# HomeBoard.net
KiCad netlist of a schematic drawn in EAGLE
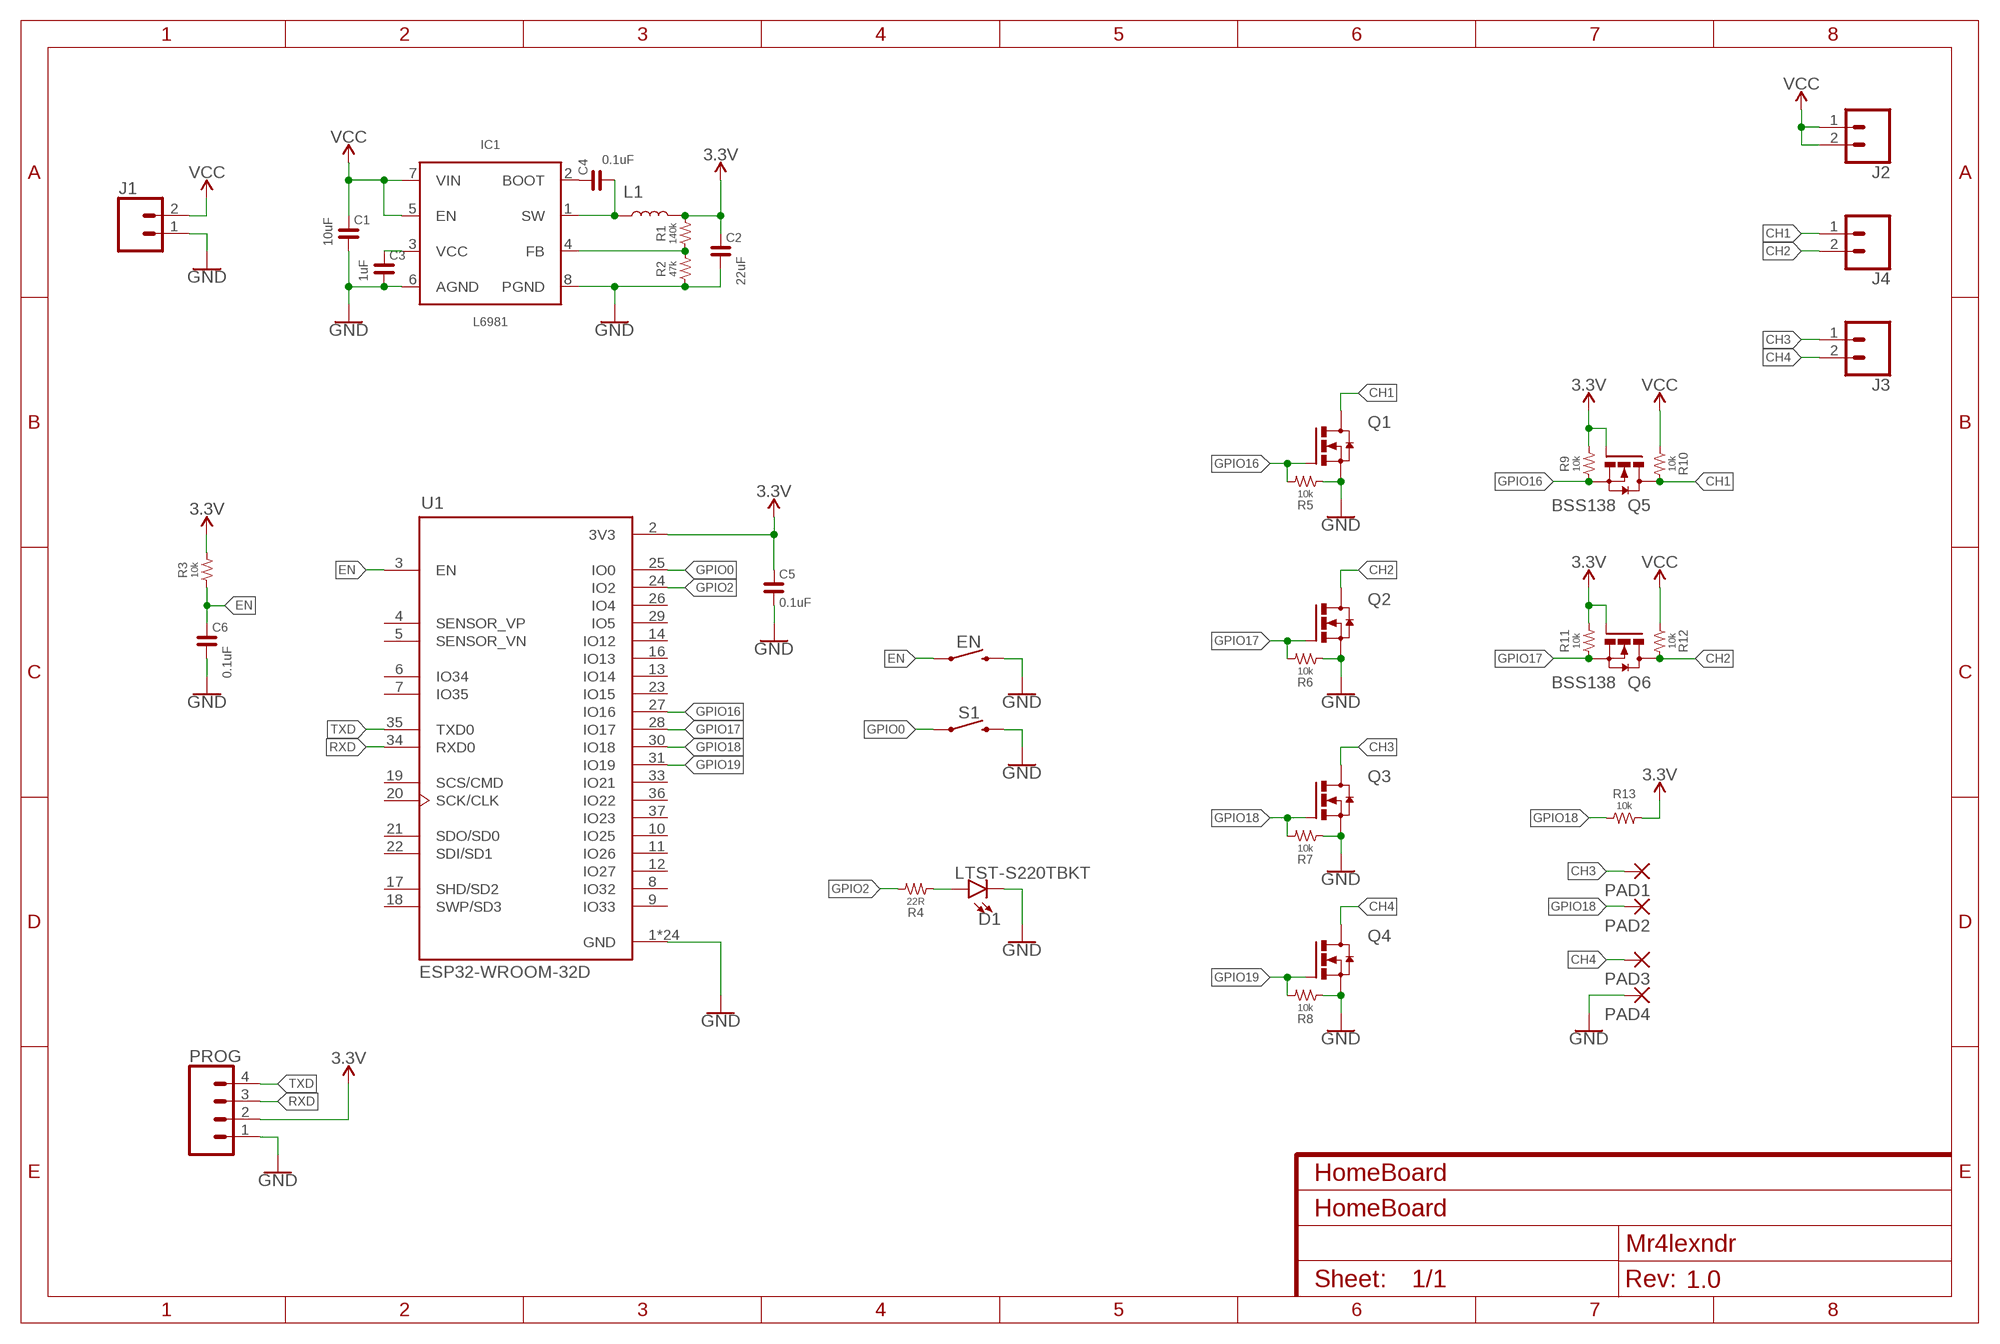
[diagram p0: schematic, sheet 1]

(export (version "E")
  (design (tool "Eeschema 10.0.6"))
  (components
    (comp (ref "C1")
      (value "10uF")
      (footprint "eagle-import:1206")
      (libsource (lib "eagle-import") (part "CAP-1206"))
    )
    (comp (ref "C2")
      (value "22uF")
      (footprint "eagle-import:1206")
      (libsource (lib "eagle-import") (part "CAP-1206"))
    )
    (comp (ref "C3")
      (value "1uF")
      (footprint "eagle-import:0603")
      (libsource (lib "eagle-import") (part "CAP-0603"))
    )
    (comp (ref "C4")
      (value "0.1uF")
      (footprint "eagle-import:0603")
      (libsource (lib "eagle-import") (part "CAP-0603"))
    )
    (comp (ref "C5")
      (value "0.1uF")
      (footprint "eagle-import:0603")
      (libsource (lib "eagle-import") (part "CAP-0603"))
    )
    (comp (ref "C6")
      (value "0.1uF")
      (footprint "eagle-import:0603")
      (libsource (lib "eagle-import") (part "CAP-0603"))
    )
    (comp (ref "D1")
      (value "LTST-S220TBKT")
      (footprint "eagle-import:LED-ANGLE-2MM")
      (libsource (lib "eagle-import") (part "LED-ANGLE-2MM"))
    )
    (comp (ref "EN")
      (value "MOMENTARY-SWITCH-SPST-SMD-6.0X3.5MM")
      (footprint "eagle-import:TACTILE_SWITCH_SMD_6.0X3.5MM")
      (libsource (lib "eagle-import") (part "MOMENTARY-SWITCH-SPST-SMD-6.0X3.5MM"))
    )
    (comp (ref "IC1")
      (value "L6981")
      (footprint "eagle-import:SO-8L")
      (libsource (lib "eagle-import") (part "L6981"))
    )
    (comp (ref "J1")
      (value "CONN_025MM")
      (footprint "eagle-import:SCREWTERMINAL-5MM-2")
      (libsource (lib "eagle-import") (part "CONN_025MM"))
    )
    (comp (ref "J2")
      (value "CONN_025MM")
      (footprint "eagle-import:SCREWTERMINAL-5MM-2")
      (libsource (lib "eagle-import") (part "CONN_025MM"))
    )
    (comp (ref "J3")
      (value "CONN_025MM")
      (footprint "eagle-import:SCREWTERMINAL-5MM-2")
      (libsource (lib "eagle-import") (part "CONN_025MM"))
    )
    (comp (ref "J4")
      (value "CONN_025MM")
      (footprint "eagle-import:SCREWTERMINAL-5MM-2")
      (libsource (lib "eagle-import") (part "CONN_025MM"))
    )
    (comp (ref "L1")
      (value "INDUCTOR-7.3X6.6")
      (footprint "eagle-import:INDUCTOR-7.3X6.6")
      (libsource (lib "eagle-import") (part "INDUCTOR-7.3X6.6"))
    )
    (comp (ref "PAD1")
      (value "SMD_PADSMD-1X1.5MM")
      (footprint "eagle-import:SMD1X1.5MM")
      (libsource (lib "eagle-import") (part "SMD_PADSMD-1X1.5MM"))
    )
    (comp (ref "PAD2")
      (value "SMD_PADSMD-1X1.5MM")
      (footprint "eagle-import:SMD1X1.5MM")
      (libsource (lib "eagle-import") (part "SMD_PADSMD-1X1.5MM"))
    )
    (comp (ref "PAD3")
      (value "SMD_PADSMD-1X1.5MM")
      (footprint "eagle-import:SMD1X1.5MM")
      (libsource (lib "eagle-import") (part "SMD_PADSMD-1X1.5MM"))
    )
    (comp (ref "PAD4")
      (value "SMD_PADSMD-1X1.5MM")
      (footprint "eagle-import:SMD1X1.5MM")
      (libsource (lib "eagle-import") (part "SMD_PADSMD-1X1.5MM"))
    )
    (comp (ref "PROG")
      (value "CONN_04LOCK")
      (footprint "eagle-import:1X04_LOCK")
      (libsource (lib "eagle-import") (part "CONN_04LOCK"))
    )
    (comp (ref "Q1")
      (value "MOSFET-N-DPAK")
      (footprint "eagle-import:D-PAK_TO252AA")
      (libsource (lib "eagle-import") (part "MOSFET-N-DPAK"))
    )
    (comp (ref "Q2")
      (value "MOSFET-N-DPAK")
      (footprint "eagle-import:D-PAK_TO252AA")
      (libsource (lib "eagle-import") (part "MOSFET-N-DPAK"))
    )
    (comp (ref "Q3")
      (value "MOSFET-N-DPAK")
      (footprint "eagle-import:D-PAK_TO252AA")
      (libsource (lib "eagle-import") (part "MOSFET-N-DPAK"))
    )
    (comp (ref "Q4")
      (value "MOSFET-N-DPAK")
      (footprint "eagle-import:D-PAK_TO252AA")
      (libsource (lib "eagle-import") (part "MOSFET-N-DPAK"))
    )
    (comp (ref "Q5")
      (value "BSS138")
      (footprint "eagle-import:SOT23-3")
      (libsource (lib "eagle-import") (part "MOSFET-N-SOT23-3"))
    )
    (comp (ref "Q6")
      (value "BSS138")
      (footprint "eagle-import:SOT23-3")
      (libsource (lib "eagle-import") (part "MOSFET-N-SOT23-3"))
    )
    (comp (ref "R1")
      (value "140k")
      (footprint "eagle-import:0603")
      (libsource (lib "eagle-import") (part "RESISTOR0603"))
    )
    (comp (ref "R2")
      (value "47k")
      (footprint "eagle-import:0603")
      (libsource (lib "eagle-import") (part "RESISTOR0603"))
    )
    (comp (ref "R3")
      (value "10k")
      (footprint "eagle-import:0603")
      (libsource (lib "eagle-import") (part "RESISTOR0603"))
    )
    (comp (ref "R4")
      (value "22R")
      (footprint "eagle-import:0603")
      (libsource (lib "eagle-import") (part "RESISTOR0603"))
    )
    (comp (ref "R5")
      (value "10k")
      (footprint "eagle-import:0603")
      (libsource (lib "eagle-import") (part "RESISTOR0603"))
    )
    (comp (ref "R6")
      (value "10k")
      (footprint "eagle-import:0603")
      (libsource (lib "eagle-import") (part "RESISTOR0603"))
    )
    (comp (ref "R7")
      (value "10k")
      (footprint "eagle-import:0603")
      (libsource (lib "eagle-import") (part "RESISTOR0603"))
    )
    (comp (ref "R8")
      (value "10k")
      (footprint "eagle-import:0603")
      (libsource (lib "eagle-import") (part "RESISTOR0603"))
    )
    (comp (ref "R9")
      (value "10k")
      (footprint "eagle-import:0603")
      (libsource (lib "eagle-import") (part "RESISTOR0603"))
    )
    (comp (ref "R10")
      (value "10k")
      (footprint "eagle-import:0603")
      (libsource (lib "eagle-import") (part "RESISTOR0603"))
    )
    (comp (ref "R11")
      (value "10k")
      (footprint "eagle-import:0603")
      (libsource (lib "eagle-import") (part "RESISTOR0603"))
    )
    (comp (ref "R12")
      (value "10k")
      (footprint "eagle-import:0603")
      (libsource (lib "eagle-import") (part "RESISTOR0603"))
    )
    (comp (ref "R13")
      (value "10k")
      (footprint "eagle-import:0603")
      (libsource (lib "eagle-import") (part "RESISTOR0603"))
    )
    (comp (ref "S1")
      (value "MOMENTARY-SWITCH-SPST-PTH-RIGHT-ANGLE-KIT")
      (footprint "eagle-import:TACTILE_SWITCH_PTH_RIGHT_ANGLE_KIT")
      (libsource (lib "eagle-import") (part "MOMENTARY-SWITCH-SPST-PTH-RIGHT-ANGLE-KIT"))
    )
    (comp (ref "U1")
      (value "ESP32-WROOM-32D")
      (footprint "eagle-import:MODULE_ESP32-WROOM-32D")
      (fields (field (name "MF") "Espressif Systems"))
      (libsource (lib "eagle-import") (part "ESP32-WROOM-32D"))
    )
  )
  (nets
    (net (code "1") (name "3.3V") (class "Default")
      (node (ref "C2") (pin "2") (pinfunction "2_2") (pintype "passive"))
      (node (ref "C5") (pin "2") (pinfunction "2_2") (pintype "passive"))
      (node (ref "L1") (pin "P$2") (pinfunction "2_P$2") (pintype "passive"))
      (node (ref "PROG") (pin "2") (pinfunction "2_2") (pintype "passive"))
      (node (ref "Q5") (pin "1") (pinfunction "G_1") (pintype "passive"))
      (node (ref "Q6") (pin "1") (pinfunction "G_1") (pintype "passive"))
      (node (ref "R1") (pin "2") (pinfunction "2_2") (pintype "passive"))
      (node (ref "R11") (pin "2") (pinfunction "2_2") (pintype "passive"))
      (node (ref "R13") (pin "2") (pinfunction "2_2") (pintype "passive"))
      (node (ref "R3") (pin "2") (pinfunction "2_2") (pintype "passive"))
      (node (ref "R9") (pin "2") (pinfunction "2_2") (pintype "passive"))
      (node (ref "U1") (pin "2") (pinfunction "3V3_2") (pintype "power_in"))
    )
    (net (code "2") (name "CH1") (class "Default")
      (node (ref "J4") (pin "1") (pinfunction "1_1") (pintype "passive"))
      (node (ref "Q1") (pin "4") (pinfunction "D_4") (pintype "passive"))
      (node (ref "Q5") (pin "3") (pinfunction "D_3") (pintype "passive"))
      (node (ref "R10") (pin "2") (pinfunction "2_2") (pintype "passive"))
    )
    (net (code "3") (name "CH2") (class "Default")
      (node (ref "J4") (pin "2") (pinfunction "2_2") (pintype "passive"))
      (node (ref "Q2") (pin "4") (pinfunction "D_4") (pintype "passive"))
      (node (ref "Q6") (pin "3") (pinfunction "D_3") (pintype "passive"))
      (node (ref "R12") (pin "2") (pinfunction "2_2") (pintype "passive"))
    )
    (net (code "4") (name "CH3") (class "Default")
      (node (ref "J3") (pin "1") (pinfunction "1_1") (pintype "passive"))
      (node (ref "PAD1") (pin "P$1") (pinfunction "P_P$1") (pintype "passive"))
      (node (ref "Q3") (pin "4") (pinfunction "D_4") (pintype "passive"))
    )
    (net (code "5") (name "CH4") (class "Default")
      (node (ref "J3") (pin "2") (pinfunction "2_2") (pintype "passive"))
      (node (ref "PAD3") (pin "P$1") (pinfunction "P_P$1") (pintype "passive"))
      (node (ref "Q4") (pin "4") (pinfunction "D_4") (pintype "passive"))
    )
    (net (code "6") (name "EN") (class "Default")
      (node (ref "C6") (pin "2") (pinfunction "2_2") (pintype "passive"))
      (node (ref "EN") (pin "1") (pinfunction "1_1") (pintype "passive"))
      (node (ref "R3") (pin "1") (pinfunction "1_1") (pintype "passive"))
      (node (ref "U1") (pin "3") (pinfunction "EN_3") (pintype "input"))
    )
    (net (code "7") (name "GND") (class "Default")
      (node (ref "C1") (pin "1") (pinfunction "1_1") (pintype "passive"))
      (node (ref "C2") (pin "1") (pinfunction "1_1") (pintype "passive"))
      (node (ref "C3") (pin "1") (pinfunction "1_1") (pintype "passive"))
      (node (ref "C5") (pin "1") (pinfunction "1_1") (pintype "passive"))
      (node (ref "C6") (pin "1") (pinfunction "1_1") (pintype "passive"))
      (node (ref "D1") (pin "C") (pinfunction "C_C") (pintype "passive"))
      (node (ref "EN") (pin "2") (pinfunction "2_2") (pintype "passive"))
      (node (ref "IC1") (pin "6") (pinfunction "AGND_6") (pintype "bidirectional"))
      (node (ref "IC1") (pin "8") (pinfunction "PGND_8") (pintype "bidirectional"))
      (node (ref "J1") (pin "1") (pinfunction "1_1") (pintype "passive"))
      (node (ref "PAD4") (pin "P$1") (pinfunction "P_P$1") (pintype "passive"))
      (node (ref "PROG") (pin "1") (pinfunction "1_1") (pintype "passive"))
      (node (ref "Q1") (pin "3") (pinfunction "S_3") (pintype "passive"))
      (node (ref "Q2") (pin "3") (pinfunction "S_3") (pintype "passive"))
      (node (ref "Q3") (pin "3") (pinfunction "S_3") (pintype "passive"))
      (node (ref "Q4") (pin "3") (pinfunction "S_3") (pintype "passive"))
      (node (ref "R2") (pin "1") (pinfunction "1_1") (pintype "passive"))
      (node (ref "R5") (pin "1") (pinfunction "1_1") (pintype "passive"))
      (node (ref "R6") (pin "1") (pinfunction "1_1") (pintype "passive"))
      (node (ref "R7") (pin "1") (pinfunction "1_1") (pintype "passive"))
      (node (ref "R8") (pin "1") (pinfunction "1_1") (pintype "passive"))
      (node (ref "S1") (pin "2") (pinfunction "2_2") (pintype "passive"))
      (node (ref "U1") (pin "1") (pinfunction "GND_1") (pintype "power_in"))
      (node (ref "U1") (pin "15") (pinfunction "GND_15") (pintype "power_in"))
      (node (ref "U1") (pin "38") (pinfunction "GND_38") (pintype "power_in"))
      (node (ref "U1") (pin "39_1") (pinfunction "GND_39_1") (pintype "power_in"))
      (node (ref "U1") (pin "39_10") (pinfunction "GND_39_10") (pintype "power_in"))
      (node (ref "U1") (pin "39_11") (pinfunction "GND_39_11") (pintype "power_in"))
      (node (ref "U1") (pin "39_12") (pinfunction "GND_39_12") (pintype "power_in"))
      (node (ref "U1") (pin "39_13") (pinfunction "GND_39_13") (pintype "power_in"))
      (node (ref "U1") (pin "39_14") (pinfunction "GND_39_14") (pintype "power_in"))
      (node (ref "U1") (pin "39_15") (pinfunction "GND_39_15") (pintype "power_in"))
      (node (ref "U1") (pin "39_16") (pinfunction "GND_39_16") (pintype "power_in"))
      (node (ref "U1") (pin "39_17") (pinfunction "GND_39_17") (pintype "power_in"))
      (node (ref "U1") (pin "39_18") (pinfunction "GND_39_18") (pintype "power_in"))
      (node (ref "U1") (pin "39_19") (pinfunction "GND_39_19") (pintype "power_in"))
      (node (ref "U1") (pin "39_2") (pinfunction "GND_39_2") (pintype "power_in"))
      (node (ref "U1") (pin "39_20") (pinfunction "GND_39_20") (pintype "power_in"))
      (node (ref "U1") (pin "39_21") (pinfunction "GND_39_21") (pintype "power_in"))
      (node (ref "U1") (pin "39_3") (pinfunction "GND_39_3") (pintype "power_in"))
      (node (ref "U1") (pin "39_4") (pinfunction "GND_39_4") (pintype "power_in"))
      (node (ref "U1") (pin "39_5") (pinfunction "GND_39_5") (pintype "power_in"))
      (node (ref "U1") (pin "39_6") (pinfunction "GND_39_6") (pintype "power_in"))
      (node (ref "U1") (pin "39_7") (pinfunction "GND_39_7") (pintype "power_in"))
      (node (ref "U1") (pin "39_8") (pinfunction "GND_39_8") (pintype "power_in"))
      (node (ref "U1") (pin "39_9") (pinfunction "GND_39_9") (pintype "power_in"))
    )
    (net (code "8") (name "GPIO0") (class "Default")
      (node (ref "S1") (pin "1") (pinfunction "1_1") (pintype "passive"))
      (node (ref "U1") (pin "25") (pinfunction "IO0_25") (pintype "bidirectional"))
    )
    (net (code "9") (name "GPIO2") (class "Default")
      (node (ref "R4") (pin "2") (pinfunction "2_2") (pintype "passive"))
      (node (ref "U1") (pin "24") (pinfunction "IO2_24") (pintype "bidirectional"))
    )
    (net (code "10") (name "GPIO16") (class "Default")
      (node (ref "Q1") (pin "1") (pinfunction "G_1") (pintype "passive"))
      (node (ref "Q5") (pin "2") (pinfunction "S_2") (pintype "passive"))
      (node (ref "R5") (pin "2") (pinfunction "2_2") (pintype "passive"))
      (node (ref "R9") (pin "1") (pinfunction "1_1") (pintype "passive"))
      (node (ref "U1") (pin "27") (pinfunction "IO16_27") (pintype "bidirectional"))
    )
    (net (code "11") (name "GPIO17") (class "Default")
      (node (ref "Q2") (pin "1") (pinfunction "G_1") (pintype "passive"))
      (node (ref "Q6") (pin "2") (pinfunction "S_2") (pintype "passive"))
      (node (ref "R11") (pin "1") (pinfunction "1_1") (pintype "passive"))
      (node (ref "R6") (pin "2") (pinfunction "2_2") (pintype "passive"))
      (node (ref "U1") (pin "28") (pinfunction "IO17_28") (pintype "bidirectional"))
    )
    (net (code "12") (name "GPIO18") (class "Default")
      (node (ref "PAD2") (pin "P$1") (pinfunction "P_P$1") (pintype "passive"))
      (node (ref "Q3") (pin "1") (pinfunction "G_1") (pintype "passive"))
      (node (ref "R13") (pin "1") (pinfunction "1_1") (pintype "passive"))
      (node (ref "R7") (pin "2") (pinfunction "2_2") (pintype "passive"))
      (node (ref "U1") (pin "30") (pinfunction "IO18_30") (pintype "bidirectional"))
    )
    (net (code "13") (name "GPIO19") (class "Default")
      (node (ref "Q4") (pin "1") (pinfunction "G_1") (pintype "passive"))
      (node (ref "R8") (pin "2") (pinfunction "2_2") (pintype "passive"))
      (node (ref "U1") (pin "31") (pinfunction "IO19_31") (pintype "bidirectional"))
    )
    (net (code "14") (name "Net-(D1-PadA)") (class "Default")
      (node (ref "D1") (pin "A") (pinfunction "A_A") (pintype "passive"))
      (node (ref "R4") (pin "1") (pinfunction "1_1") (pintype "passive"))
    )
    (net (code "15") (name "Net-(IC1-BOOT)") (class "Default")
      (node (ref "C4") (pin "2") (pinfunction "2_2") (pintype "passive"))
      (node (ref "IC1") (pin "2") (pinfunction "BOOT_2") (pintype "bidirectional"))
    )
    (net (code "16") (name "Net-(IC1-FB)") (class "Default")
      (node (ref "IC1") (pin "4") (pinfunction "FB_4") (pintype "bidirectional"))
      (node (ref "R1") (pin "1") (pinfunction "1_1") (pintype "passive"))
      (node (ref "R2") (pin "2") (pinfunction "2_2") (pintype "passive"))
    )
    (net (code "17") (name "Net-(IC1-SW)") (class "Default")
      (node (ref "C4") (pin "1") (pinfunction "1_1") (pintype "passive"))
      (node (ref "IC1") (pin "1") (pinfunction "SW_1") (pintype "bidirectional"))
      (node (ref "L1") (pin "P$1") (pinfunction "1_P$1") (pintype "passive"))
    )
    (net (code "18") (name "Net-(IC1-VCC)") (class "Default")
      (node (ref "C3") (pin "2") (pinfunction "2_2") (pintype "passive"))
      (node (ref "IC1") (pin "3") (pinfunction "VCC_3") (pintype "bidirectional"))
    )
    (net (code "19") (name "RXD") (class "Default")
      (node (ref "PROG") (pin "3") (pinfunction "3_3") (pintype "passive"))
      (node (ref "U1") (pin "34") (pinfunction "RXD0_34") (pintype "bidirectional"))
    )
    (net (code "20") (name "TXD") (class "Default")
      (node (ref "PROG") (pin "4") (pinfunction "4_4") (pintype "passive"))
      (node (ref "U1") (pin "35") (pinfunction "TXD0_35") (pintype "bidirectional"))
    )
    (net (code "21") (name "VCC") (class "Default")
      (node (ref "C1") (pin "2") (pinfunction "2_2") (pintype "passive"))
      (node (ref "IC1") (pin "5") (pinfunction "EN_5") (pintype "bidirectional"))
      (node (ref "IC1") (pin "7") (pinfunction "VIN_7") (pintype "bidirectional"))
      (node (ref "J1") (pin "2") (pinfunction "2_2") (pintype "passive"))
      (node (ref "J2") (pin "1") (pinfunction "1_1") (pintype "passive"))
      (node (ref "J2") (pin "2") (pinfunction "2_2") (pintype "passive"))
      (node (ref "R10") (pin "1") (pinfunction "1_1") (pintype "passive"))
      (node (ref "R12") (pin "1") (pinfunction "1_1") (pintype "passive"))
    )
    (net (code "22") (name "unconnected-(U1-IO4-Pad26)") (class "Default")
      (node (ref "U1") (pin "26") (pinfunction "IO4_26") (pintype "bidirectional"))
    )
    (net (code "23") (name "unconnected-(U1-IO5-Pad29)") (class "Default")
      (node (ref "U1") (pin "29") (pinfunction "IO5_29") (pintype "bidirectional"))
    )
    (net (code "24") (name "unconnected-(U1-IO12-Pad14)") (class "Default")
      (node (ref "U1") (pin "14") (pinfunction "IO12_14") (pintype "bidirectional"))
    )
    (net (code "25") (name "unconnected-(U1-IO13-Pad16)") (class "Default")
      (node (ref "U1") (pin "16") (pinfunction "IO13_16") (pintype "bidirectional"))
    )
    (net (code "26") (name "unconnected-(U1-IO14-Pad13)") (class "Default")
      (node (ref "U1") (pin "13") (pinfunction "IO14_13") (pintype "bidirectional"))
    )
    (net (code "27") (name "unconnected-(U1-IO15-Pad23)") (class "Default")
      (node (ref "U1") (pin "23") (pinfunction "IO15_23") (pintype "bidirectional"))
    )
    (net (code "28") (name "unconnected-(U1-IO21-Pad33)") (class "Default")
      (node (ref "U1") (pin "33") (pinfunction "IO21_33") (pintype "bidirectional"))
    )
    (net (code "29") (name "unconnected-(U1-IO22-Pad36)") (class "Default")
      (node (ref "U1") (pin "36") (pinfunction "IO22_36") (pintype "bidirectional"))
    )
    (net (code "30") (name "unconnected-(U1-IO23-Pad37)") (class "Default")
      (node (ref "U1") (pin "37") (pinfunction "IO23_37") (pintype "bidirectional"))
    )
    (net (code "31") (name "unconnected-(U1-IO25-Pad10)") (class "Default")
      (node (ref "U1") (pin "10") (pinfunction "IO25_10") (pintype "bidirectional"))
    )
    (net (code "32") (name "unconnected-(U1-IO26-Pad11)") (class "Default")
      (node (ref "U1") (pin "11") (pinfunction "IO26_11") (pintype "bidirectional"))
    )
    (net (code "33") (name "unconnected-(U1-IO27-Pad12)") (class "Default")
      (node (ref "U1") (pin "12") (pinfunction "IO27_12") (pintype "bidirectional"))
    )
    (net (code "34") (name "unconnected-(U1-IO32-Pad8)") (class "Default")
      (node (ref "U1") (pin "8") (pinfunction "IO32_8") (pintype "bidirectional"))
    )
    (net (code "35") (name "unconnected-(U1-IO33-Pad9)") (class "Default")
      (node (ref "U1") (pin "9") (pinfunction "IO33_9") (pintype "bidirectional"))
    )
    (net (code "36") (name "unconnected-(U1-IO34-Pad6)") (class "Default")
      (node (ref "U1") (pin "6") (pinfunction "IO34_6") (pintype "input"))
    )
    (net (code "37") (name "unconnected-(U1-IO35-Pad7)") (class "Default")
      (node (ref "U1") (pin "7") (pinfunction "IO35_7") (pintype "input"))
    )
    (net (code "38") (name "unconnected-(U1-SCK{slash}CLK-Pad20)") (class "Default")
      (node (ref "U1") (pin "20") (pinfunction "SCK/CLK_20") (pintype "bidirectional"))
    )
    (net (code "39") (name "unconnected-(U1-SCS{slash}CMD-Pad19)") (class "Default")
      (node (ref "U1") (pin "19") (pinfunction "SCS/CMD_19") (pintype "bidirectional"))
    )
    (net (code "40") (name "unconnected-(U1-SDI{slash}SD1-Pad22)") (class "Default")
      (node (ref "U1") (pin "22") (pinfunction "SDI/SD1_22") (pintype "bidirectional"))
    )
    (net (code "41") (name "unconnected-(U1-SDO{slash}SD0-Pad21)") (class "Default")
      (node (ref "U1") (pin "21") (pinfunction "SDO/SD0_21") (pintype "bidirectional"))
    )
    (net (code "42") (name "unconnected-(U1-SENSOR_VN-Pad5)") (class "Default")
      (node (ref "U1") (pin "5") (pinfunction "SENSOR_VN_5") (pintype "input"))
    )
    (net (code "43") (name "unconnected-(U1-SENSOR_VP-Pad4)") (class "Default")
      (node (ref "U1") (pin "4") (pinfunction "SENSOR_VP_4") (pintype "input"))
    )
    (net (code "44") (name "unconnected-(U1-SHD{slash}SD2-Pad17)") (class "Default")
      (node (ref "U1") (pin "17") (pinfunction "SHD/SD2_17") (pintype "bidirectional"))
    )
    (net (code "45") (name "unconnected-(U1-SWP{slash}SD3-Pad18)") (class "Default")
      (node (ref "U1") (pin "18") (pinfunction "SWP/SD3_18") (pintype "bidirectional"))
    )
  )
)
